# hvreg_feedback_2PS_ACDC.net
KiCad netlist of a schematic drawn in EAGLE
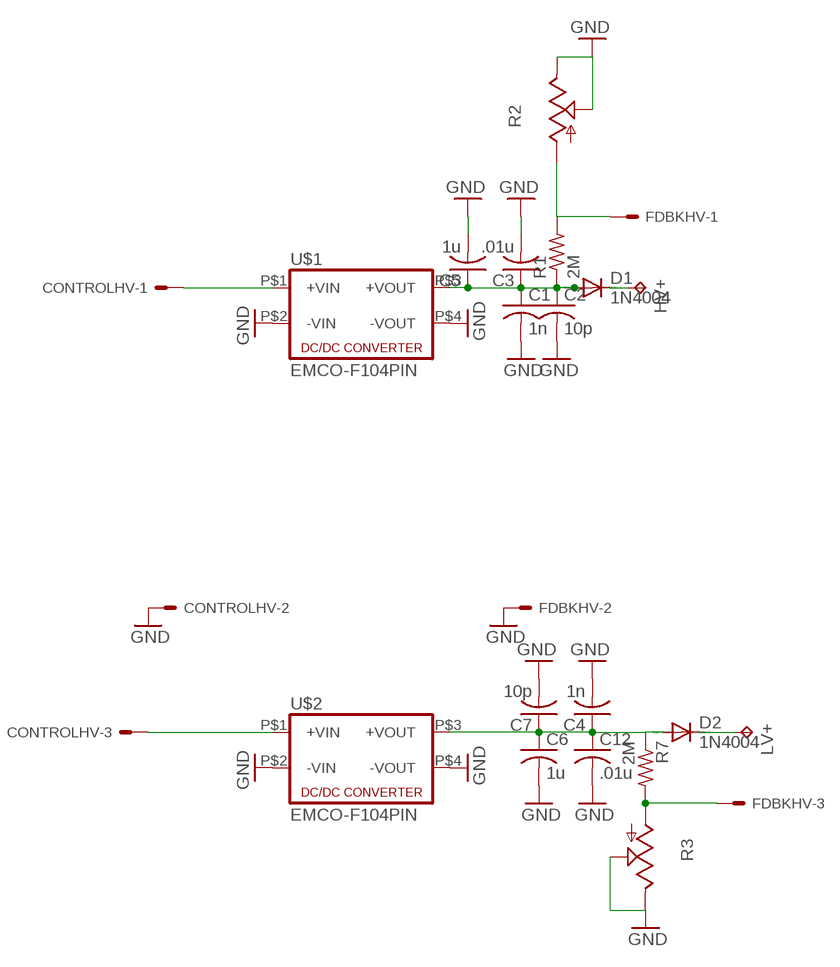
[diagram p0: schematic, sheet 1]

(export (version "E")
  (design (tool "Eeschema 10.0.6"))
  (components
    (comp (ref "C1")
      (value "1n")
      (footprint "eagle-import:C075-042X103")
      (libsource (lib "eagle-import") (part "C-US075-042X103"))
    )
    (comp (ref "C2")
      (value "10p")
      (footprint "eagle-import:C075-042X103")
      (libsource (lib "eagle-import") (part "C-US075-042X103"))
    )
    (comp (ref "C3")
      (value ".01u")
      (footprint "eagle-import:C075-042X103")
      (libsource (lib "eagle-import") (part "C-US075-042X103"))
    )
    (comp (ref "C4")
      (value "1n")
      (footprint "eagle-import:C075-042X103")
      (libsource (lib "eagle-import") (part "C-US075-042X103"))
    )
    (comp (ref "C5")
      (value "1u")
      (footprint "eagle-import:C275-205X316")
      (libsource (lib "eagle-import") (part "C-US275-205X316"))
    )
    (comp (ref "C6")
      (value "1u")
      (footprint "eagle-import:C275-205X316")
      (libsource (lib "eagle-import") (part "C-US275-205X316"))
    )
    (comp (ref "C7")
      (value "10p")
      (footprint "eagle-import:C075-042X103")
      (libsource (lib "eagle-import") (part "C-US075-042X103"))
    )
    (comp (ref "C12")
      (value ".01u")
      (footprint "eagle-import:C075-042X103")
      (libsource (lib "eagle-import") (part "C-US075-042X103"))
    )
    (comp (ref "CONTROLHV")
      (value "KK-156-3")
      (footprint "eagle-import:KK-156-3")
      (libsource (lib "eagle-import") (part "KK-156-3"))
    )
    (comp (ref "D1")
      (value "1N4004")
      (footprint "eagle-import:DO41-10")
      (libsource (lib "eagle-import") (part "1N4004"))
    )
    (comp (ref "D2")
      (value "1N4004")
      (footprint "eagle-import:DO41-10")
      (libsource (lib "eagle-import") (part "1N4004"))
    )
    (comp (ref "FDBKHV")
      (value "KK-156-3")
      (footprint "eagle-import:KK-156-3")
      (libsource (lib "eagle-import") (part "KK-156-3"))
    )
    (comp (ref "HV+")
      (value "TPPAD1-20Y")
      (footprint "eagle-import:P1-20Y")
      (libsource (lib "eagle-import") (part "TPPAD1-20Y"))
    )
    (comp (ref "LV+")
      (value "TPPAD1-20Y")
      (footprint "eagle-import:P1-20Y")
      (libsource (lib "eagle-import") (part "TPPAD1-20Y"))
    )
    (comp (ref "R1")
      (value "2M")
      (footprint "eagle-import:0207_12")
      (libsource (lib "eagle-import") (part "R-US_0207/12"))
    )
    (comp (ref "R2")
      (value "TRIM_US-B90P")
      (footprint "eagle-import:SP19L")
      (libsource (lib "eagle-import") (part "TRIM_US-B90P"))
    )
    (comp (ref "R3")
      (value "TRIM_US-B90P")
      (footprint "eagle-import:SP19L")
      (libsource (lib "eagle-import") (part "TRIM_US-B90P"))
    )
    (comp (ref "R7")
      (value "2M")
      (footprint "eagle-import:0207_12")
      (libsource (lib "eagle-import") (part "R-US_0207/12"))
    )
    (comp (ref "U$1")
      (value "EMCO-F104PIN")
      (footprint "eagle-import:EMCO-F")
      (libsource (lib "eagle-import") (part "EMCO-F104PIN"))
    )
    (comp (ref "U$2")
      (value "EMCO-F104PIN")
      (footprint "eagle-import:EMCO-F")
      (libsource (lib "eagle-import") (part "EMCO-F104PIN"))
    )
  )
  (nets
    (net (code "1") (name "GND") (class "Default")
      (node (ref "C1") (pin "2") (pinfunction "2_2") (pintype "passive"))
      (node (ref "C12") (pin "2") (pinfunction "2_2") (pintype "passive"))
      (node (ref "C2") (pin "2") (pinfunction "2_2") (pintype "passive"))
      (node (ref "C3") (pin "2") (pinfunction "2_2") (pintype "passive"))
      (node (ref "C4") (pin "2") (pinfunction "2_2") (pintype "passive"))
      (node (ref "C5") (pin "2") (pinfunction "2_2") (pintype "passive"))
      (node (ref "C6") (pin "2") (pinfunction "2_2") (pintype "passive"))
      (node (ref "C7") (pin "2") (pinfunction "2_2") (pintype "passive"))
      (node (ref "CONTROLHV") (pin "2") (pinfunction "S_2") (pintype "passive"))
      (node (ref "FDBKHV") (pin "2") (pinfunction "S_2") (pintype "passive"))
      (node (ref "R2") (pin "E") (pinfunction "E_E") (pintype "passive"))
      (node (ref "R2") (pin "S") (pinfunction "S_S") (pintype "passive"))
      (node (ref "R3") (pin "E") (pinfunction "E_E") (pintype "passive"))
      (node (ref "R3") (pin "S") (pinfunction "S_S") (pintype "passive"))
      (node (ref "U$1") (pin "P$2") (pinfunction "-VIN_P$2") (pintype "passive"))
      (node (ref "U$1") (pin "P$4") (pinfunction "-VOUT_P$4") (pintype "passive"))
      (node (ref "U$2") (pin "P$2") (pinfunction "-VIN_P$2") (pintype "passive"))
      (node (ref "U$2") (pin "P$4") (pinfunction "-VOUT_P$4") (pintype "passive"))
    )
    (net (code "2") (name "Net-(CONTROLHVA-S)") (class "Default")
      (node (ref "CONTROLHV") (pin "1") (pinfunction "S_1") (pintype "passive"))
      (node (ref "U$1") (pin "P$1") (pinfunction "+VIN_P$1") (pintype "passive"))
    )
    (net (code "3") (name "Net-(CONTROLHVC-S)") (class "Default")
      (node (ref "CONTROLHV") (pin "3") (pinfunction "S_3") (pintype "passive"))
      (node (ref "U$2") (pin "P$1") (pinfunction "+VIN_P$1") (pintype "passive"))
    )
    (net (code "4") (name "Net-(D1-PadC)") (class "Default")
      (node (ref "D1") (pin "C") (pinfunction "C_C") (pintype "passive"))
      (node (ref "HV+") (pin "TP") (pinfunction "TP_TP") (pintype "input"))
    )
    (net (code "5") (name "Net-(D2-PadC)") (class "Default")
      (node (ref "D2") (pin "C") (pinfunction "C_C") (pintype "passive"))
      (node (ref "LV+") (pin "TP") (pinfunction "TP_TP") (pintype "input"))
    )
    (net (code "6") (name "Net-(FDBKHVA-S)") (class "Default")
      (node (ref "FDBKHV") (pin "1") (pinfunction "S_1") (pintype "passive"))
      (node (ref "R1") (pin "2") (pinfunction "2_2") (pintype "passive"))
      (node (ref "R2") (pin "A") (pinfunction "A_A") (pintype "passive"))
    )
    (net (code "7") (name "Net-(FDBKHVC-S)") (class "Default")
      (node (ref "FDBKHV") (pin "3") (pinfunction "S_3") (pintype "passive"))
      (node (ref "R3") (pin "A") (pinfunction "A_A") (pintype "passive"))
      (node (ref "R7") (pin "2") (pinfunction "2_2") (pintype "passive"))
    )
    (net (code "8") (name "Net-(U$1-+VOUT)") (class "Default")
      (node (ref "C1") (pin "1") (pinfunction "1_1") (pintype "passive"))
      (node (ref "C2") (pin "1") (pinfunction "1_1") (pintype "passive"))
      (node (ref "C3") (pin "1") (pinfunction "1_1") (pintype "passive"))
      (node (ref "C5") (pin "1") (pinfunction "1_1") (pintype "passive"))
      (node (ref "D1") (pin "A") (pinfunction "A_A") (pintype "passive"))
      (node (ref "R1") (pin "1") (pinfunction "1_1") (pintype "passive"))
      (node (ref "U$1") (pin "P$3") (pinfunction "+VOUT_P$3") (pintype "passive"))
    )
    (net (code "9") (name "Net-(U$2-+VOUT)") (class "Default")
      (node (ref "C12") (pin "1") (pinfunction "1_1") (pintype "passive"))
      (node (ref "C4") (pin "1") (pinfunction "1_1") (pintype "passive"))
      (node (ref "C6") (pin "1") (pinfunction "1_1") (pintype "passive"))
      (node (ref "C7") (pin "1") (pinfunction "1_1") (pintype "passive"))
      (node (ref "D2") (pin "A") (pinfunction "A_A") (pintype "passive"))
      (node (ref "R7") (pin "1") (pinfunction "1_1") (pintype "passive"))
      (node (ref "U$2") (pin "P$3") (pinfunction "+VOUT_P$3") (pintype "passive"))
    )
  )
)
